# Sheet1.net
KiCad netlist of a schematic drawn in Altium Designer
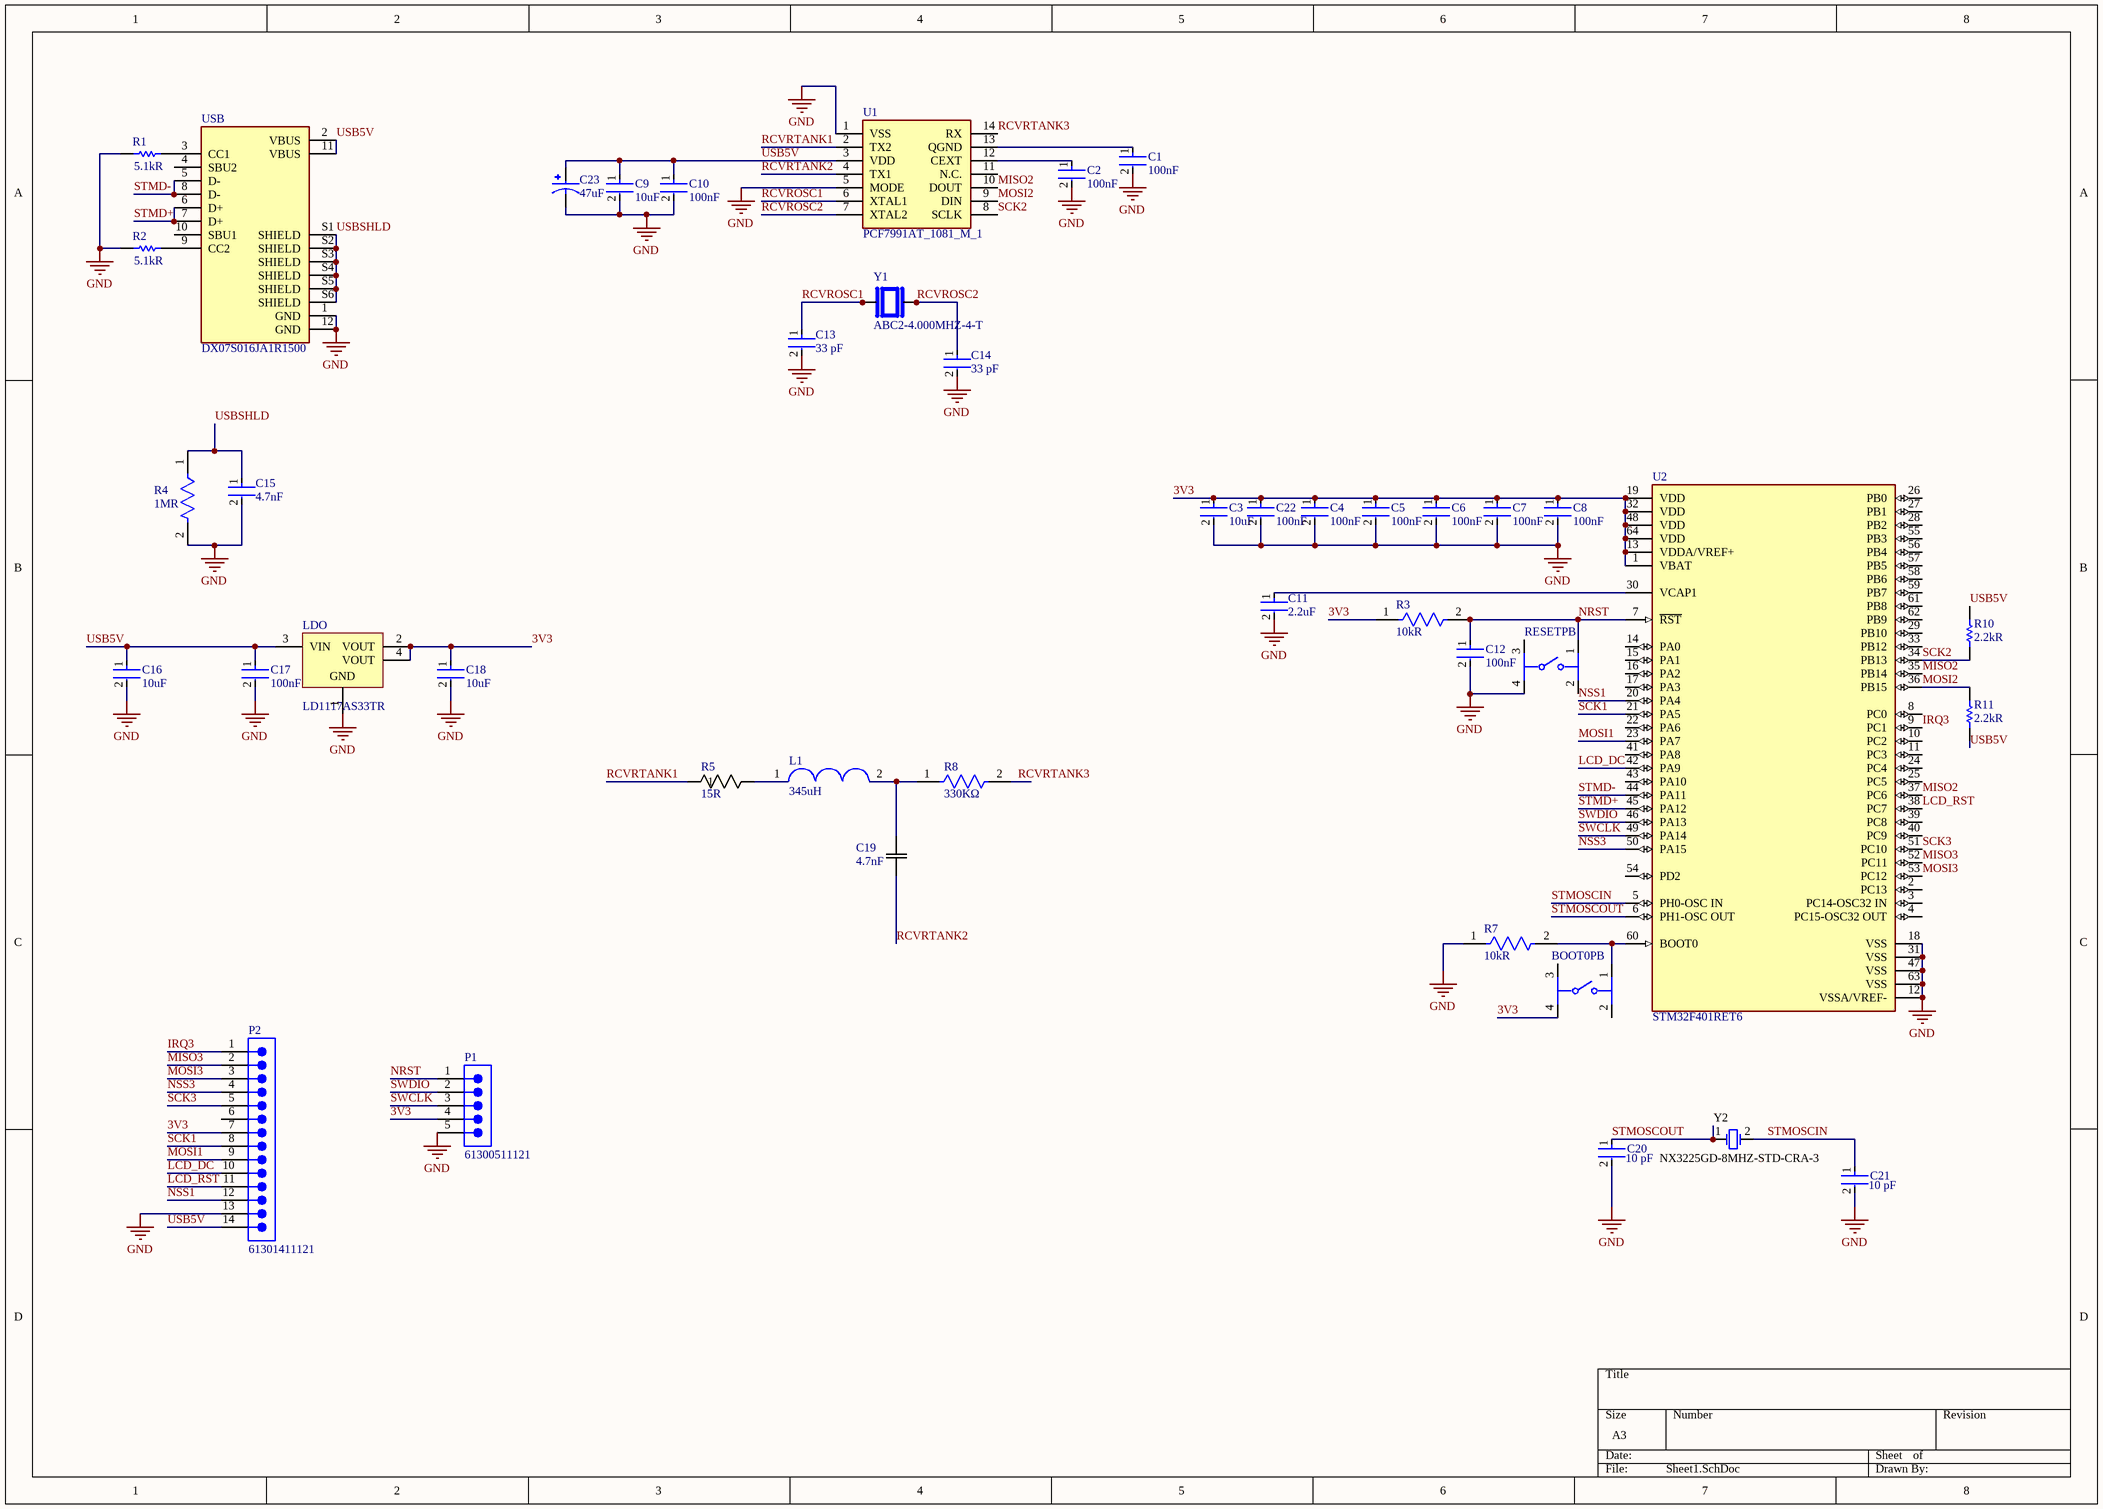
[diagram p0: Sheet1.SchDoc]

(export (version "E")
  (design (tool "Eeschema 10.0.6"))
  (components
    (comp (ref "BOOT0PB")
      (value "PTS647SM38SMTR2LFS")
      (footprint "FP-PTS647SM38SMTR2LFS-MFG")
      (description "TACT 4.5 X 4.5, 3.8 MM H, 1.8N,")
      (libsource (lib "Altium Content Vault") (part "1adf0dd01260c80cf25a44bfd6b99ba"))
    )
    (comp (ref "C1")
      (value "C0603C104K5RACTU")
      (footprint "FP-C0603C-CF-MFG")
      (description "CAP CER 0.1UF 50V X7R 0603")
      (fields
        (field (name "TOLERANCE") "0.1")
        (field (name "MANUFACTURER") "KEMET")
        (field (name "CAPACITANCE") "100nF")
      )
      (libsource (lib "Altium Content Vault") (part "b4654b650e69147ec39a6b967a45e02"))
    )
    (comp (ref "C2")
      (value "C0603C104K5RACTU")
      (footprint "FP-C0603C-CF-MFG")
      (description "CAP CER 0.1UF 50V X7R 0603")
      (fields
        (field (name "TOLERANCE") "0.1")
        (field (name "MANUFACTURER") "KEMET")
        (field (name "CAPACITANCE") "100nF")
      )
      (libsource (lib "Altium Content Vault") (part "b4654b650e69147ec39a6b967a45e02"))
    )
    (comp (ref "C3")
      (value "GRM188R6YA106MA73D")
      (footprint "FP-GRM188-0_2-IPC_C")
      (description "Chip Multilayer Ceramic Capacitors for General Purpose, 0603, 10uF, X5R, 15%, 20%, 35V")
      (fields (field (name "CAPACITANCE") "10uF") (field (name "TOLERANCE") "20%"))
      (libsource (lib "Altium Content Vault") (part "11868f565c42a9108669ba33697ecf6"))
    )
    (comp (ref "C4")
      (value "C0603C104K5RACTU")
      (footprint "FP-C0603C-CF-MFG")
      (description "CAP CER 0.1UF 50V X7R 0603")
      (fields
        (field (name "TOLERANCE") "0.1")
        (field (name "MANUFACTURER") "KEMET")
        (field (name "CAPACITANCE") "100nF")
      )
      (libsource (lib "Altium Content Vault") (part "b4654b650e69147ec39a6b967a45e02"))
    )
    (comp (ref "C5")
      (value "C0603C104K5RACTU")
      (footprint "FP-C0603C-CF-MFG")
      (description "CAP CER 0.1UF 50V X7R 0603")
      (fields
        (field (name "TOLERANCE") "0.1")
        (field (name "MANUFACTURER") "KEMET")
        (field (name "CAPACITANCE") "100nF")
      )
      (libsource (lib "Altium Content Vault") (part "b4654b650e69147ec39a6b967a45e02"))
    )
    (comp (ref "C6")
      (value "C0603C104K5RACTU")
      (footprint "FP-C0603C-CF-MFG")
      (description "CAP CER 0.1UF 50V X7R 0603")
      (fields
        (field (name "TOLERANCE") "0.1")
        (field (name "MANUFACTURER") "KEMET")
        (field (name "CAPACITANCE") "100nF")
      )
      (libsource (lib "Altium Content Vault") (part "b4654b650e69147ec39a6b967a45e02"))
    )
    (comp (ref "C7")
      (value "C0603C104K5RACTU")
      (footprint "FP-C0603C-CF-MFG")
      (description "CAP CER 0.1UF 50V X7R 0603")
      (fields
        (field (name "TOLERANCE") "0.1")
        (field (name "MANUFACTURER") "KEMET")
        (field (name "CAPACITANCE") "100nF")
      )
      (libsource (lib "Altium Content Vault") (part "b4654b650e69147ec39a6b967a45e02"))
    )
    (comp (ref "C8")
      (value "C0603C104K5RACTU")
      (footprint "FP-C0603C-CF-MFG")
      (description "CAP CER 0.1UF 50V X7R 0603")
      (fields
        (field (name "TOLERANCE") "0.1")
        (field (name "MANUFACTURER") "KEMET")
        (field (name "CAPACITANCE") "100nF")
      )
      (libsource (lib "Altium Content Vault") (part "b4654b650e69147ec39a6b967a45e02"))
    )
    (comp (ref "C9")
      (value "GRM188R6YA106MA73D")
      (footprint "FP-GRM188-0_2-IPC_C")
      (description "Chip Multilayer Ceramic Capacitors for General Purpose, 0603, 10uF, X5R, 15%, 20%, 35V")
      (fields (field (name "CAPACITANCE") "10uF") (field (name "TOLERANCE") "20%"))
      (libsource (lib "Altium Content Vault") (part "11868f565c42a9108669ba33697ecf6"))
    )
    (comp (ref "C10")
      (value "C0603C104K5RACTU")
      (footprint "FP-C0603C-CF-MFG")
      (description "CAP CER 0.1UF 50V X7R 0603")
      (fields
        (field (name "TOLERANCE") "0.1")
        (field (name "MANUFACTURER") "KEMET")
        (field (name "CAPACITANCE") "100nF")
      )
      (libsource (lib "Altium Content Vault") (part "b4654b650e69147ec39a6b967a45e02"))
    )
    (comp (ref "C11")
      (value "CL10A225KO8NNNC")
      (footprint "FP-CL10-IPC_A")
      (description "Cap Ceramic 2.2uF 16V X5R ±10% Pad SMD 0603 +85°C T/R")
      (fields
        (field (name "CAPACITANCE") "2.2uF")
        (field (name "TOLERANCE") "10%")
        (field (name "VOLTAGE") "16V")
      )
      (libsource (lib "Altium Content Vault") (part "b4654b650e69147ec39a6b967a45e02"))
    )
    (comp (ref "C12")
      (value "C0603C104K5RACTU")
      (footprint "FP-C0603C-CF-MFG")
      (description "CAP CER 0.1UF 50V X7R 0603")
      (fields
        (field (name "TOLERANCE") "0.1")
        (field (name "MANUFACTURER") "KEMET")
        (field (name "CAPACITANCE") "100nF")
      )
      (libsource (lib "Altium Content Vault") (part "b4654b650e69147ec39a6b967a45e02"))
    )
    (comp (ref "C13")
      (value "33 pF")
      (footprint "FP-C0603C-CF-MFG")
      (description "Capacitor; Ceramic; Cap; 33.0pF; Tol 5%; SMT; Vol-Rtg 50V; C0G; Tape and Reel")
      (fields (field (name "MANUFACTURER PART NUMBER") "C0603C330J5GACTU") (field (name "TOLERANCE") "0.05"))
      (libsource (lib "Altium Content Vault") (part "b4654b650e69147ec39a6b967a45e02"))
    )
    (comp (ref "C14")
      (value "33 pF")
      (footprint "FP-C0603C-CF-MFG")
      (description "Capacitor; Ceramic; Cap; 33.0pF; Tol 5%; SMT; Vol-Rtg 50V; C0G; Tape and Reel")
      (fields (field (name "MANUFACTURER PART NUMBER") "C0603C330J5GACTU") (field (name "TOLERANCE") "0.05"))
      (libsource (lib "Altium Content Vault") (part "b4654b650e69147ec39a6b967a45e02"))
    )
    (comp (ref "C15")
      (value "GRM1885C1H472JA01D")
      (footprint "FP-GRM188-0_1-e0_2_0_5-MFG")
      (description "Chip Multilayer Ceramic Capacitors for General Purpose, 0603, 4700pF, C0G, 30ppm/°C, 5%, 50V")
      (fields (field (name "CAPACITANCE") "4.7nF") (field (name "TOLERANCE") "5%"))
      (libsource (lib "Altium Content Vault") (part "11868f565c42a9108669ba33697ecf6"))
    )
    (comp (ref "C16")
      (value "GRM188R6YA106MA73D")
      (footprint "FP-GRM188-0_2-IPC_C")
      (description "Chip Multilayer Ceramic Capacitors for General Purpose, 0603, 10uF, X5R, 15%, 20%, 35V")
      (fields (field (name "CAPACITANCE") "10uF") (field (name "TOLERANCE") "20%"))
      (libsource (lib "Altium Content Vault") (part "11868f565c42a9108669ba33697ecf6"))
    )
    (comp (ref "C17")
      (value "C0603C104K5RACTU")
      (footprint "FP-C0603C-CF-MFG")
      (description "CAP CER 0.1UF 50V X7R 0603")
      (fields
        (field (name "TOLERANCE") "0.1")
        (field (name "MANUFACTURER") "KEMET")
        (field (name "CAPACITANCE") "100nF")
      )
      (libsource (lib "Altium Content Vault") (part "b4654b650e69147ec39a6b967a45e02"))
    )
    (comp (ref "C18")
      (value "GRM188R6YA106MA73D")
      (footprint "FP-GRM188-0_2-IPC_C")
      (description "Chip Multilayer Ceramic Capacitors for General Purpose, 0603, 10uF, X5R, 15%, 20%, 35V")
      (fields (field (name "CAPACITANCE") "10uF") (field (name "TOLERANCE") "20%"))
      (libsource (lib "Altium Content Vault") (part "11868f565c42a9108669ba33697ecf6"))
    )
    (comp (ref "C19")
      (value "C1206C472FBGACTU")
      (footprint "CAPC340180_110N_KEM")
      (fields
        (field (name "PARAMETER 1") "4.7nF")
        (field (name "COPYRIGHT") "Copyright (C) 2026 Ultra Librarian. All rights reserved.")
      )
      (libsource (lib "richardDongAlitumDesigner") (part "C1206C472FBGACTU"))
    )
    (comp (ref "C20")
      (value "C0603C100J5GACTU")
      (footprint "FP-C0603C-CF-MFG")
      (description "CAP CER 10PF 50V C0G/NP0 0603")
      (fields
        (field (name "CAPACITANCE") "10 pF")
        (field (name "OCTOPART") "https://octopart.com/c0603c100j5gactu-kemet-138281")
        (field (name "MANUFACTURER") "KEMET")
      )
      (libsource (lib "Altium Content Vault") (part "b4654b650e69147ec39a6b967a45e02"))
    )
    (comp (ref "C21")
      (value "C0603C100J5GACTU")
      (footprint "FP-C0603C-CF-MFG")
      (description "CAP CER 10PF 50V C0G/NP0 0603")
      (fields
        (field (name "CAPACITANCE") "10 pF")
        (field (name "OCTOPART") "https://octopart.com/c0603c100j5gactu-kemet-138281")
        (field (name "MANUFACTURER") "KEMET")
      )
      (libsource (lib "Altium Content Vault") (part "b4654b650e69147ec39a6b967a45e02"))
    )
    (comp (ref "C22")
      (value "C0603C104K5RACTU")
      (footprint "FP-C0603C-CF-MFG")
      (description "CAP CER 0.1UF 50V X7R 0603")
      (fields
        (field (name "TOLERANCE") "0.1")
        (field (name "MANUFACTURER") "KEMET")
        (field (name "CAPACITANCE") "100nF")
      )
      (libsource (lib "Altium Content Vault") (part "b4654b650e69147ec39a6b967a45e02"))
    )
    (comp (ref "C23")
      (value "47uF")
      (footprint "CAP_EEEFK1C470P")
      (description "47ÂµF 16V Aluminum Electrolytic Capacitors Radial, Can - SMD 2000 Hrs @ 105Â°C")
      (fields (field (name "MF") "Panasonic Electronic") (field (name "MP") "EEE-FK1C470P"))
      (libsource (lib "EEEFK1C470P") (part "EEEFK1C470P"))
    )
    (comp (ref "L1")
      (value "CP-345UH-ID20")
      (footprint "CP-345UH-ID20")
      (fields (field (name "PARAMETER 1") "345uH"))
      (libsource (lib "Schlib1") (part "CP-345UH-ID20"))
    )
    (comp (ref "LDO")
      (value "LD1117AS33TR")
      (footprint "SOT-223_M")
      (description "1A, Low Drop Positive Voltage Regulator, 3.3V, 4-Pin SOT-223, Tape and Reel")
      (libsource (lib "Altium Content Vault") (part "PM-REG-LD1117-SOT4"))
    )
    (comp (ref "P1")
      (value "61300511121")
      (footprint "61300511121")
      (description "THT Vertical Pin Header WR-PHD, Pitch 2.54 mm, Single Row, 5 pins")
      (libsource (lib "Altium Content Vault") (part "Header_Male_1R_05P"))
    )
    (comp (ref "P2")
      (value "61301411121")
      (footprint "61301411121")
      (description "THT Vertical Pin Header WR-PHD, Pitch 2.54 mm, Single Row, 14 pins")
      (libsource (lib "Altium Content Vault") (part "Header_Male_1R_14P"))
    )
    (comp (ref "R1")
      (value "RC0603FR-075K1L")
      (footprint "RESC1608X55X25ML10T15")
      (fields (field (name "MANUFACTURER") "Yageo") (field (name "PARAMETER 1") "5.1kR"))
      (libsource (lib "Altium Content Vault") (part "RES"))
    )
    (comp (ref "R2")
      (value "RC0603FR-075K1L")
      (footprint "RESC1608X55X25ML10T15")
      (fields (field (name "MANUFACTURER") "Yageo") (field (name "PARAMETER 1") "5.1kR"))
      (libsource (lib "Altium Content Vault") (part "RES"))
    )
    (comp (ref "R3")
      (value "RC0603FR-0710KL")
      (footprint "FP-RC0603-0_55-IPC_C")
      (description "RES 10K OHM 1% 1/10W 0603")
      (fields (field (name "TOLERANCE") "1%") (field (name "RESISTANCE") "10kR"))
      (libsource (lib "Altium Content Vault") (part "1029c3af85768c4190bb7ad29bc67b5"))
    )
    (comp (ref "R4")
      (value "ERJ-3EKF1004V")
      (footprint "FP-ERJ3EK-IPC_C")
      (description "RES SMD 1M OHM 1% 1/10W 0603")
      (fields (field (name "TOLERANCE") "1%") (field (name "RESISTANCE") "1MR"))
      (libsource (lib "Altium Content Vault") (part "1029c3af85768c4190bb7ad29bc67b5"))
    )
    (comp (ref "R5")
      (value "352115RFT")
      (footprint "RES_352115RFT_TEC")
      (description "3521 15R 1% 2W")
      (fields
        (field (name "PARAMETER 1") "15R")
        (field (name "COPYRIGHT") "Copyright (C) 2026 Ultra Librarian. All rights reserved.")
      )
      (libsource (lib "richardDongAlitumDesigner") (part "352115RFT"))
    )
    (comp (ref "R7")
      (value "RC0603FR-0710KL")
      (footprint "FP-RC0603-0_55-IPC_C")
      (description "RES 10K OHM 1% 1/10W 0603")
      (fields (field (name "TOLERANCE") "1%") (field (name "RESISTANCE") "10kR"))
      (libsource (lib "Altium Content Vault") (part "1029c3af85768c4190bb7ad29bc67b5"))
    )
    (comp (ref "R8")
      (value "CRGCQ1206F330K")
      (footprint "FP-CRGCQ1206-IPC_C")
      (description "CRGCQ1206 330KΩ 0.25W 1% ±100ppm/°C 200V")
      (fields
        (field (name "RESISTANCE") "330KΩ")
        (field (name "OCTOPART") "https://octopart.com/crgcq1206f330k-te+connectivity-91018273")
        (field (name "MANUFACTURER") "TE Connectivity")
      )
      (libsource (lib "Altium Content Vault") (part "1029c3af85768c4190bb7ad29bc67b5"))
    )
    (comp (ref "R10")
      (value "RC0603FR-072K2L")
      (footprint "RESC1608X55X25LL10T15")
      (fields
        (field (name "TOLERANCE") "1%")
        (field (name "RESISTANCE") "2.2kR")
        (field (name "MANUFACTURER") "Yageo")
      )
      (libsource (lib "Altium Content Vault") (part "RES-2"))
    )
    (comp (ref "R11")
      (value "RC0603FR-072K2L")
      (footprint "RESC1608X55X25LL10T15")
      (fields
        (field (name "TOLERANCE") "1%")
        (field (name "RESISTANCE") "2.2kR")
        (field (name "MANUFACTURER") "Yageo")
      )
      (libsource (lib "Altium Content Vault") (part "RES-2"))
    )
    (comp (ref "RESETPB")
      (value "PTS647SM38SMTR2LFS")
      (footprint "FP-PTS647SM38SMTR2LFS-MFG")
      (description "TACT 4.5 X 4.5, 3.8 MM H, 1.8N,")
      (libsource (lib "Altium Content Vault") (part "1adf0dd01260c80cf25a44bfd6b99ba"))
    )
    (comp (ref "U1")
      (value "PCF7991AT_1081_M_1")
      (footprint "SOIC127P600X175-14N")
      (description "IC REMOTE KEYLESS ENTRY 14SOIC")
      (fields (field (name "MANUFACTURER_PART_NUMBER") "PCF7991AT/1081/M:1"))
      (libsource (lib "richardDongAlitumDesigner") (part "PCF7991AT_1081_M_1"))
    )
    (comp (ref "U2")
      (value "STM32F401RET6")
      (footprint "FP-LQFP64-5W-MFG")
      (description "IC MCU 32BIT 512KB FLASH 64LQFP")
      (fields
        (field (name "OCTOPART") "https://octopart.com/stm32f401ret6-stmicroelectronics-34185993")
        (field (name "MANUFACTURER") "STMicroelectronics")
      )
      (libsource (lib "Altium Content Vault") (part "7f49e7cdc56bbeda8d86db7d775c506"))
    )
    (comp (ref "USB")
      (value "DX07S016JA1R1500")
      (footprint "JAE_DX07S016JA1R1500")
      (libsource (lib "DX07S016JA1R1500") (part "DX07S016JA1R1500"))
    )
    (comp (ref "Y1")
      (value "ABC2-4.000MHZ-4-T")
      (footprint "XTAL_ABC2-4.000MHZ-4-T")
      (libsource (lib "ABC2-4.000MHZ-4-T") (part "ABC2-4.000MHZ-4-T"))
    )
    (comp (ref "Y2")
      (value "NX3225GD-8MHZ-STD-CRA-3")
      (footprint "NDK-NX3225GD-8MHZ-STD-CRA-3_V")
      (description "Crystal Unit, 8 MHz, 8 pF, -40 to 150 degC, 2-Pin SMD, RoHS, Tape and Reel")
      (fields (field (name "MANUFACTURER") "NDK"))
      (libsource (lib "Altium Content Vault") (part "XTAL-1-2-2"))
    )
  )
  (nets
    (net (code "1") (name "/3V3") (class "Default")
      (node (ref "BOOT0PB") (pin "4") (pinfunction "4_4") (pintype "passive"))
      (node (ref "C18") (pin "1") (pinfunction "1_1") (pintype "passive"))
      (node (ref "C22") (pin "1") (pinfunction "1_1") (pintype "passive"))
      (node (ref "C3") (pin "1") (pinfunction "1_1") (pintype "passive"))
      (node (ref "C4") (pin "1") (pinfunction "1_1") (pintype "passive"))
      (node (ref "C5") (pin "1") (pinfunction "1_1") (pintype "passive"))
      (node (ref "C6") (pin "1") (pinfunction "1_1") (pintype "passive"))
      (node (ref "C7") (pin "1") (pinfunction "1_1") (pintype "passive"))
      (node (ref "C8") (pin "1") (pinfunction "1_1") (pintype "passive"))
      (node (ref "LDO") (pin "2") (pinfunction "VOUT_2") (pintype "power_in"))
      (node (ref "LDO") (pin "4") (pinfunction "VOUT_4") (pintype "power_in"))
      (node (ref "P1") (pin "4") (pinfunction "4_4") (pintype "passive"))
      (node (ref "P2") (pin "7") (pinfunction "7_7") (pintype "passive"))
      (node (ref "R3") (pin "1") (pinfunction "1_1") (pintype "passive"))
      (node (ref "U2") (pin "1") (pinfunction "VBAT_1") (pintype "power_in"))
      (node (ref "U2") (pin "13") (pinfunction "VDDA/VREF+_13") (pintype "power_in"))
      (node (ref "U2") (pin "19") (pinfunction "VDD_19") (pintype "power_in"))
      (node (ref "U2") (pin "32") (pinfunction "VDD_32") (pintype "power_in"))
      (node (ref "U2") (pin "48") (pinfunction "VDD_48") (pintype "power_in"))
      (node (ref "U2") (pin "64") (pinfunction "VDD_64") (pintype "power_in"))
    )
    (net (code "2") (name "/IRQ3") (class "Default")
      (node (ref "P2") (pin "1") (pinfunction "1_1") (pintype "passive"))
      (node (ref "U2") (pin "9") (pinfunction "PC1_9") (pintype "bidirectional"))
    )
    (net (code "3") (name "/LCD_DC") (class "Default")
      (node (ref "P2") (pin "10") (pinfunction "10_10") (pintype "passive"))
      (node (ref "U2") (pin "42") (pinfunction "PA9_42") (pintype "bidirectional"))
    )
    (net (code "4") (name "/LCD_RST") (class "Default")
      (node (ref "P2") (pin "11") (pinfunction "11_11") (pintype "passive"))
      (node (ref "U2") (pin "38") (pinfunction "PC7_38") (pintype "bidirectional"))
    )
    (net (code "5") (name "/MISO2") (class "Default")
      (node (ref "U1") (pin "10") (pinfunction "DOUT_10") (pintype "passive"))
      (node (ref "U2") (pin "35") (pinfunction "PB14_35") (pintype "bidirectional"))
      (node (ref "U2") (pin "37") (pinfunction "PC6_37") (pintype "bidirectional"))
    )
    (net (code "6") (name "/MISO3") (class "Default")
      (node (ref "P2") (pin "2") (pinfunction "2_2") (pintype "passive"))
      (node (ref "U2") (pin "52") (pinfunction "PC11_52") (pintype "bidirectional"))
    )
    (net (code "7") (name "/MOSI1") (class "Default")
      (node (ref "P2") (pin "9") (pinfunction "9_9") (pintype "passive"))
      (node (ref "U2") (pin "23") (pinfunction "PA7_23") (pintype "bidirectional"))
    )
    (net (code "8") (name "/MOSI2") (class "Default")
      (node (ref "R11") (pin "2") (pinfunction "2_2") (pintype "passive"))
      (node (ref "U1") (pin "9") (pinfunction "DIN_9") (pintype "passive"))
      (node (ref "U2") (pin "36") (pinfunction "PB15_36") (pintype "bidirectional"))
    )
    (net (code "9") (name "/MOSI3") (class "Default")
      (node (ref "P2") (pin "3") (pinfunction "3_3") (pintype "passive"))
      (node (ref "U2") (pin "53") (pinfunction "PC12_53") (pintype "bidirectional"))
    )
    (net (code "10") (name "/NRST") (class "Default")
      (node (ref "C12") (pin "1") (pinfunction "1_1") (pintype "passive"))
      (node (ref "P1") (pin "1") (pinfunction "1_1") (pintype "passive"))
      (node (ref "R3") (pin "2") (pinfunction "2_2") (pintype "passive"))
      (node (ref "RESETPB") (pin "1") (pinfunction "1_1") (pintype "passive"))
      (node (ref "U2") (pin "7") (pinfunction "~{RST}_7") (pintype "input"))
    )
    (net (code "11") (name "/NSS1") (class "Default")
      (node (ref "P2") (pin "12") (pinfunction "12_12") (pintype "passive"))
      (node (ref "U2") (pin "20") (pinfunction "PA4_20") (pintype "bidirectional"))
    )
    (net (code "12") (name "/NSS3") (class "Default")
      (node (ref "P2") (pin "4") (pinfunction "4_4") (pintype "passive"))
      (node (ref "U2") (pin "50") (pinfunction "PA15_50") (pintype "bidirectional"))
    )
    (net (code "13") (name "/RCVROSC1") (class "Default")
      (node (ref "C13") (pin "1") (pinfunction "1_1") (pintype "passive"))
      (node (ref "U1") (pin "6") (pinfunction "XTAL1_6") (pintype "passive"))
      (node (ref "Y1") (pin "1") (pinfunction "1_1") (pintype "passive"))
      (node (ref "Y1") (pin "4") (pinfunction "1_4") (pintype "passive"))
    )
    (net (code "14") (name "/RCVROSC2") (class "Default")
      (node (ref "C14") (pin "1") (pinfunction "1_1") (pintype "passive"))
      (node (ref "U1") (pin "7") (pinfunction "XTAL2_7") (pintype "passive"))
      (node (ref "Y1") (pin "2") (pinfunction "2_2") (pintype "passive"))
      (node (ref "Y1") (pin "3") (pinfunction "2_3") (pintype "passive"))
    )
    (net (code "15") (name "/RCVRTANK1") (class "Default")
      (node (ref "R5") (pin "1") (pinfunction "1_1") (pintype "passive"))
      (node (ref "U1") (pin "2") (pinfunction "TX2_2") (pintype "passive"))
    )
    (net (code "16") (name "/RCVRTANK2") (class "Default")
      (node (ref "C19") (pin "1") (pinfunction "1_1") (pintype "passive"))
      (node (ref "U1") (pin "4") (pinfunction "TX1_4") (pintype "passive"))
    )
    (net (code "17") (name "/RCVRTANK3") (class "Default")
      (node (ref "R8") (pin "2") (pinfunction "2_2") (pintype "passive"))
      (node (ref "U1") (pin "14") (pinfunction "RX_14") (pintype "passive"))
    )
    (net (code "18") (name "/SCK1") (class "Default")
      (node (ref "P2") (pin "8") (pinfunction "8_8") (pintype "passive"))
      (node (ref "U2") (pin "21") (pinfunction "PA5_21") (pintype "bidirectional"))
    )
    (net (code "19") (name "/SCK2") (class "Default")
      (node (ref "R10") (pin "1") (pinfunction "1_1") (pintype "passive"))
      (node (ref "U1") (pin "8") (pinfunction "SCLK_8") (pintype "passive"))
      (node (ref "U2") (pin "34") (pinfunction "PB13_34") (pintype "bidirectional"))
    )
    (net (code "20") (name "/SCK3") (class "Default")
      (node (ref "P2") (pin "5") (pinfunction "5_5") (pintype "passive"))
      (node (ref "U2") (pin "51") (pinfunction "PC10_51") (pintype "bidirectional"))
    )
    (net (code "21") (name "/STMD+") (class "Default")
      (node (ref "U2") (pin "45") (pinfunction "PA12_45") (pintype "bidirectional"))
      (node (ref "USB") (pin "6") (pinfunction "D+_6") (pintype "passive"))
      (node (ref "USB") (pin "7") (pinfunction "D+_7") (pintype "passive"))
    )
    (net (code "22") (name "/STMD-") (class "Default")
      (node (ref "U2") (pin "44") (pinfunction "PA11_44") (pintype "bidirectional"))
      (node (ref "USB") (pin "5") (pinfunction "D-_5") (pintype "passive"))
      (node (ref "USB") (pin "8") (pinfunction "D-_8") (pintype "passive"))
    )
    (net (code "23") (name "/STMOSCIN") (class "Default")
      (node (ref "C21") (pin "1") (pinfunction "1_1") (pintype "passive"))
      (node (ref "U2") (pin "5") (pinfunction "PH0-OSC_IN_5") (pintype "bidirectional"))
      (node (ref "Y2") (pin "2") (pinfunction "2_2") (pintype "passive"))
    )
    (net (code "24") (name "/STMOSCOUT") (class "Default")
      (node (ref "C20") (pin "1") (pinfunction "1_1") (pintype "passive"))
      (node (ref "U2") (pin "6") (pinfunction "PH1-OSC_OUT_6") (pintype "bidirectional"))
      (node (ref "Y2") (pin "1") (pinfunction "1_1") (pintype "passive"))
    )
    (net (code "25") (name "/SWCLK") (class "Default")
      (node (ref "P1") (pin "3") (pinfunction "3_3") (pintype "passive"))
      (node (ref "U2") (pin "49") (pinfunction "PA14_49") (pintype "bidirectional"))
    )
    (net (code "26") (name "/SWDIO") (class "Default")
      (node (ref "P1") (pin "2") (pinfunction "2_2") (pintype "passive"))
      (node (ref "U2") (pin "46") (pinfunction "PA13_46") (pintype "bidirectional"))
    )
    (net (code "27") (name "/USB5V") (class "Default")
      (node (ref "C10") (pin "1") (pinfunction "1_1") (pintype "passive"))
      (node (ref "C16") (pin "1") (pinfunction "1_1") (pintype "passive"))
      (node (ref "C17") (pin "1") (pinfunction "1_1") (pintype "passive"))
      (node (ref "C23") (pin "1") (pinfunction "1_1") (pintype "passive"))
      (node (ref "C9") (pin "1") (pinfunction "1_1") (pintype "passive"))
      (node (ref "LDO") (pin "3") (pinfunction "VIN_3") (pintype "power_in"))
      (node (ref "P2") (pin "14") (pinfunction "14_14") (pintype "passive"))
      (node (ref "R10") (pin "2") (pinfunction "2_2") (pintype "passive"))
      (node (ref "R11") (pin "1") (pinfunction "1_1") (pintype "passive"))
      (node (ref "U1") (pin "3") (pinfunction "VDD_3") (pintype "passive"))
      (node (ref "USB") (pin "11") (pinfunction "VBUS_11") (pintype "power_in"))
      (node (ref "USB") (pin "2") (pinfunction "VBUS_2") (pintype "power_in"))
    )
    (net (code "28") (name "/USBSHLD") (class "Default")
      (node (ref "C15") (pin "1") (pinfunction "1_1") (pintype "passive"))
      (node (ref "R4") (pin "1") (pinfunction "1_1") (pintype "passive"))
      (node (ref "USB") (pin "S1") (pinfunction "SHIELD_S1") (pintype "passive"))
      (node (ref "USB") (pin "S2") (pinfunction "SHIELD_S2") (pintype "passive"))
      (node (ref "USB") (pin "S3") (pinfunction "SHIELD_S3") (pintype "passive"))
      (node (ref "USB") (pin "S4") (pinfunction "SHIELD_S4") (pintype "passive"))
      (node (ref "USB") (pin "S5") (pinfunction "SHIELD_S5") (pintype "passive"))
      (node (ref "USB") (pin "S6") (pinfunction "SHIELD_S6") (pintype "passive"))
    )
    (net (code "29") (name "GND") (class "Default")
      (node (ref "C1") (pin "2") (pinfunction "2_2") (pintype "passive"))
      (node (ref "C10") (pin "2") (pinfunction "2_2") (pintype "passive"))
      (node (ref "C11") (pin "2") (pinfunction "2_2") (pintype "passive"))
      (node (ref "C12") (pin "2") (pinfunction "2_2") (pintype "passive"))
      (node (ref "C13") (pin "2") (pinfunction "2_2") (pintype "passive"))
      (node (ref "C14") (pin "2") (pinfunction "2_2") (pintype "passive"))
      (node (ref "C15") (pin "2") (pinfunction "2_2") (pintype "passive"))
      (node (ref "C16") (pin "2") (pinfunction "2_2") (pintype "passive"))
      (node (ref "C17") (pin "2") (pinfunction "2_2") (pintype "passive"))
      (node (ref "C18") (pin "2") (pinfunction "2_2") (pintype "passive"))
      (node (ref "C2") (pin "2") (pinfunction "2_2") (pintype "passive"))
      (node (ref "C20") (pin "2") (pinfunction "2_2") (pintype "passive"))
      (node (ref "C21") (pin "2") (pinfunction "2_2") (pintype "passive"))
      (node (ref "C22") (pin "2") (pinfunction "2_2") (pintype "passive"))
      (node (ref "C23") (pin "2") (pinfunction "2_2") (pintype "passive"))
      (node (ref "C3") (pin "2") (pinfunction "2_2") (pintype "passive"))
      (node (ref "C4") (pin "2") (pinfunction "2_2") (pintype "passive"))
      (node (ref "C5") (pin "2") (pinfunction "2_2") (pintype "passive"))
      (node (ref "C6") (pin "2") (pinfunction "2_2") (pintype "passive"))
      (node (ref "C7") (pin "2") (pinfunction "2_2") (pintype "passive"))
      (node (ref "C8") (pin "2") (pinfunction "2_2") (pintype "passive"))
      (node (ref "C9") (pin "2") (pinfunction "2_2") (pintype "passive"))
      (node (ref "LDO") (pin "1") (pinfunction "GND_1") (pintype "power_in"))
      (node (ref "P1") (pin "5") (pinfunction "5_5") (pintype "passive"))
      (node (ref "P2") (pin "13") (pinfunction "13_13") (pintype "passive"))
      (node (ref "R1") (pin "1") (pinfunction "1_1") (pintype "passive"))
      (node (ref "R2") (pin "1") (pinfunction "1_1") (pintype "passive"))
      (node (ref "R4") (pin "2") (pinfunction "2_2") (pintype "passive"))
      (node (ref "R7") (pin "1") (pinfunction "1_1") (pintype "passive"))
      (node (ref "RESETPB") (pin "4") (pinfunction "4_4") (pintype "passive"))
      (node (ref "U1") (pin "1") (pinfunction "VSS_1") (pintype "passive"))
      (node (ref "U1") (pin "5") (pinfunction "MODE_5") (pintype "passive"))
      (node (ref "U2") (pin "12") (pinfunction "VSSA/VREF-_12") (pintype "power_in"))
      (node (ref "U2") (pin "18") (pinfunction "VSS_18") (pintype "power_in"))
      (node (ref "U2") (pin "31") (pinfunction "VSS_31") (pintype "power_in"))
      (node (ref "U2") (pin "47") (pinfunction "VSS_47") (pintype "power_in"))
      (node (ref "U2") (pin "63") (pinfunction "VSS_63") (pintype "power_in"))
      (node (ref "USB") (pin "1") (pinfunction "GND_1") (pintype "power_in"))
      (node (ref "USB") (pin "12") (pinfunction "GND_12") (pintype "power_in"))
    )
    (net (code "30") (name "Net-(C19-Pad2)") (class "Default")
      (node (ref "C19") (pin "2") (pinfunction "2_2") (pintype "passive"))
      (node (ref "L1") (pin "2") (pintype "passive"))
      (node (ref "R8") (pin "1") (pinfunction "1_1") (pintype "passive"))
    )
    (net (code "31") (name "Net-(L1-Pad1)") (class "Default")
      (node (ref "L1") (pin "1") (pintype "passive"))
      (node (ref "R5") (pin "2") (pinfunction "2_2") (pintype "passive"))
    )
    (net (code "32") (name "Net-(U1-CEXT)") (class "Default")
      (node (ref "C2") (pin "1") (pinfunction "1_1") (pintype "passive"))
      (node (ref "U1") (pin "12") (pinfunction "CEXT_12") (pintype "passive"))
    )
    (net (code "33") (name "Net-(U1-QGND)") (class "Default")
      (node (ref "C1") (pin "1") (pinfunction "1_1") (pintype "passive"))
      (node (ref "U1") (pin "13") (pinfunction "QGND_13") (pintype "passive"))
    )
    (net (code "34") (name "Net-(U2-BOOT0)") (class "Default")
      (node (ref "BOOT0PB") (pin "1") (pinfunction "1_1") (pintype "passive"))
      (node (ref "R7") (pin "2") (pinfunction "2_2") (pintype "passive"))
      (node (ref "U2") (pin "60") (pinfunction "BOOT0_60") (pintype "input"))
    )
    (net (code "35") (name "Net-(U2-VCAP1)") (class "Default")
      (node (ref "C11") (pin "1") (pinfunction "1_1") (pintype "passive"))
      (node (ref "U2") (pin "30") (pinfunction "VCAP1_30") (pintype "power_in"))
    )
    (net (code "36") (name "Net-(USB-CC1)") (class "Default")
      (node (ref "R1") (pin "2") (pinfunction "2_2") (pintype "passive"))
      (node (ref "USB") (pin "3") (pinfunction "CC1_3") (pintype "passive"))
    )
    (net (code "37") (name "Net-(USB-CC2)") (class "Default")
      (node (ref "R2") (pin "2") (pinfunction "2_2") (pintype "passive"))
      (node (ref "USB") (pin "9") (pinfunction "CC2_9") (pintype "passive"))
    )
    (net (code "38") (name "unconnected-(BOOT0PB-Pad2)") (class "Default")
      (node (ref "BOOT0PB") (pin "2") (pinfunction "2_2") (pintype "passive"))
    )
    (net (code "39") (name "unconnected-(BOOT0PB-Pad3)") (class "Default")
      (node (ref "BOOT0PB") (pin "3") (pinfunction "3_3") (pintype "passive"))
    )
    (net (code "40") (name "unconnected-(P2-Pad6)") (class "Default")
      (node (ref "P2") (pin "6") (pinfunction "6_6") (pintype "passive"))
    )
    (net (code "41") (name "unconnected-(RESETPB-Pad2)") (class "Default")
      (node (ref "RESETPB") (pin "2") (pinfunction "2_2") (pintype "passive"))
    )
    (net (code "42") (name "unconnected-(RESETPB-Pad3)") (class "Default")
      (node (ref "RESETPB") (pin "3") (pinfunction "3_3") (pintype "passive"))
    )
    (net (code "43") (name "unconnected-(U1-N.C.-Pad11)") (class "Default")
      (node (ref "U1") (pin "11") (pinfunction "N.C._11") (pintype "passive"))
    )
    (net (code "44") (name "unconnected-(U2-PA0-Pad14)") (class "Default")
      (node (ref "U2") (pin "14") (pinfunction "PA0_14") (pintype "bidirectional"))
    )
    (net (code "45") (name "unconnected-(U2-PA1-Pad15)") (class "Default")
      (node (ref "U2") (pin "15") (pinfunction "PA1_15") (pintype "bidirectional"))
    )
    (net (code "46") (name "unconnected-(U2-PA2-Pad16)") (class "Default")
      (node (ref "U2") (pin "16") (pinfunction "PA2_16") (pintype "bidirectional"))
    )
    (net (code "47") (name "unconnected-(U2-PA3-Pad17)") (class "Default")
      (node (ref "U2") (pin "17") (pinfunction "PA3_17") (pintype "bidirectional"))
    )
    (net (code "48") (name "unconnected-(U2-PA6-Pad22)") (class "Default")
      (node (ref "U2") (pin "22") (pinfunction "PA6_22") (pintype "bidirectional"))
    )
    (net (code "49") (name "unconnected-(U2-PA8-Pad41)") (class "Default")
      (node (ref "U2") (pin "41") (pinfunction "PA8_41") (pintype "bidirectional"))
    )
    (net (code "50") (name "unconnected-(U2-PA10-Pad43)") (class "Default")
      (node (ref "U2") (pin "43") (pinfunction "PA10_43") (pintype "bidirectional"))
    )
    (net (code "51") (name "unconnected-(U2-PB0-Pad26)") (class "Default")
      (node (ref "U2") (pin "26") (pinfunction "PB0_26") (pintype "bidirectional"))
    )
    (net (code "52") (name "unconnected-(U2-PB1-Pad27)") (class "Default")
      (node (ref "U2") (pin "27") (pinfunction "PB1_27") (pintype "bidirectional"))
    )
    (net (code "53") (name "unconnected-(U2-PB2-Pad28)") (class "Default")
      (node (ref "U2") (pin "28") (pinfunction "PB2_28") (pintype "bidirectional"))
    )
    (net (code "54") (name "unconnected-(U2-PB3-Pad55)") (class "Default")
      (node (ref "U2") (pin "55") (pinfunction "PB3_55") (pintype "bidirectional"))
    )
    (net (code "55") (name "unconnected-(U2-PB4-Pad56)") (class "Default")
      (node (ref "U2") (pin "56") (pinfunction "PB4_56") (pintype "bidirectional"))
    )
    (net (code "56") (name "unconnected-(U2-PB5-Pad57)") (class "Default")
      (node (ref "U2") (pin "57") (pinfunction "PB5_57") (pintype "bidirectional"))
    )
    (net (code "57") (name "unconnected-(U2-PB6-Pad58)") (class "Default")
      (node (ref "U2") (pin "58") (pinfunction "PB6_58") (pintype "bidirectional"))
    )
    (net (code "58") (name "unconnected-(U2-PB7-Pad59)") (class "Default")
      (node (ref "U2") (pin "59") (pinfunction "PB7_59") (pintype "bidirectional"))
    )
    (net (code "59") (name "unconnected-(U2-PB8-Pad61)") (class "Default")
      (node (ref "U2") (pin "61") (pinfunction "PB8_61") (pintype "bidirectional"))
    )
    (net (code "60") (name "unconnected-(U2-PB9-Pad62)") (class "Default")
      (node (ref "U2") (pin "62") (pinfunction "PB9_62") (pintype "bidirectional"))
    )
    (net (code "61") (name "unconnected-(U2-PB10-Pad29)") (class "Default")
      (node (ref "U2") (pin "29") (pinfunction "PB10_29") (pintype "bidirectional"))
    )
    (net (code "62") (name "unconnected-(U2-PB12-Pad33)") (class "Default")
      (node (ref "U2") (pin "33") (pinfunction "PB12_33") (pintype "bidirectional"))
    )
    (net (code "63") (name "unconnected-(U2-PC0-Pad8)") (class "Default")
      (node (ref "U2") (pin "8") (pinfunction "PC0_8") (pintype "bidirectional"))
    )
    (net (code "64") (name "unconnected-(U2-PC2-Pad10)") (class "Default")
      (node (ref "U2") (pin "10") (pinfunction "PC2_10") (pintype "bidirectional"))
    )
    (net (code "65") (name "unconnected-(U2-PC3-Pad11)") (class "Default")
      (node (ref "U2") (pin "11") (pinfunction "PC3_11") (pintype "bidirectional"))
    )
    (net (code "66") (name "unconnected-(U2-PC4-Pad24)") (class "Default")
      (node (ref "U2") (pin "24") (pinfunction "PC4_24") (pintype "bidirectional"))
    )
    (net (code "67") (name "unconnected-(U2-PC5-Pad25)") (class "Default")
      (node (ref "U2") (pin "25") (pinfunction "PC5_25") (pintype "bidirectional"))
    )
    (net (code "68") (name "unconnected-(U2-PC8-Pad39)") (class "Default")
      (node (ref "U2") (pin "39") (pinfunction "PC8_39") (pintype "bidirectional"))
    )
    (net (code "69") (name "unconnected-(U2-PC9-Pad40)") (class "Default")
      (node (ref "U2") (pin "40") (pinfunction "PC9_40") (pintype "bidirectional"))
    )
    (net (code "70") (name "unconnected-(U2-PC13-Pad2)") (class "Default")
      (node (ref "U2") (pin "2") (pinfunction "PC13_2") (pintype "bidirectional"))
    )
    (net (code "71") (name "unconnected-(U2-PC14-OSC32_IN-Pad3)") (class "Default")
      (node (ref "U2") (pin "3") (pinfunction "PC14-OSC32_IN_3") (pintype "bidirectional"))
    )
    (net (code "72") (name "unconnected-(U2-PC15-OSC32_OUT-Pad4)") (class "Default")
      (node (ref "U2") (pin "4") (pinfunction "PC15-OSC32_OUT_4") (pintype "bidirectional"))
    )
    (net (code "73") (name "unconnected-(U2-PD2-Pad54)") (class "Default")
      (node (ref "U2") (pin "54") (pinfunction "PD2_54") (pintype "bidirectional"))
    )
    (net (code "74") (name "unconnected-(USB-SBU1-Pad10)") (class "Default")
      (node (ref "USB") (pin "10") (pinfunction "SBU1_10") (pintype "passive"))
    )
    (net (code "75") (name "unconnected-(USB-SBU2-Pad4)") (class "Default")
      (node (ref "USB") (pin "4") (pinfunction "SBU2_4") (pintype "passive"))
    )
  )
)
